# pd15.net
KiCad netlist of a schematic drawn in EAGLE
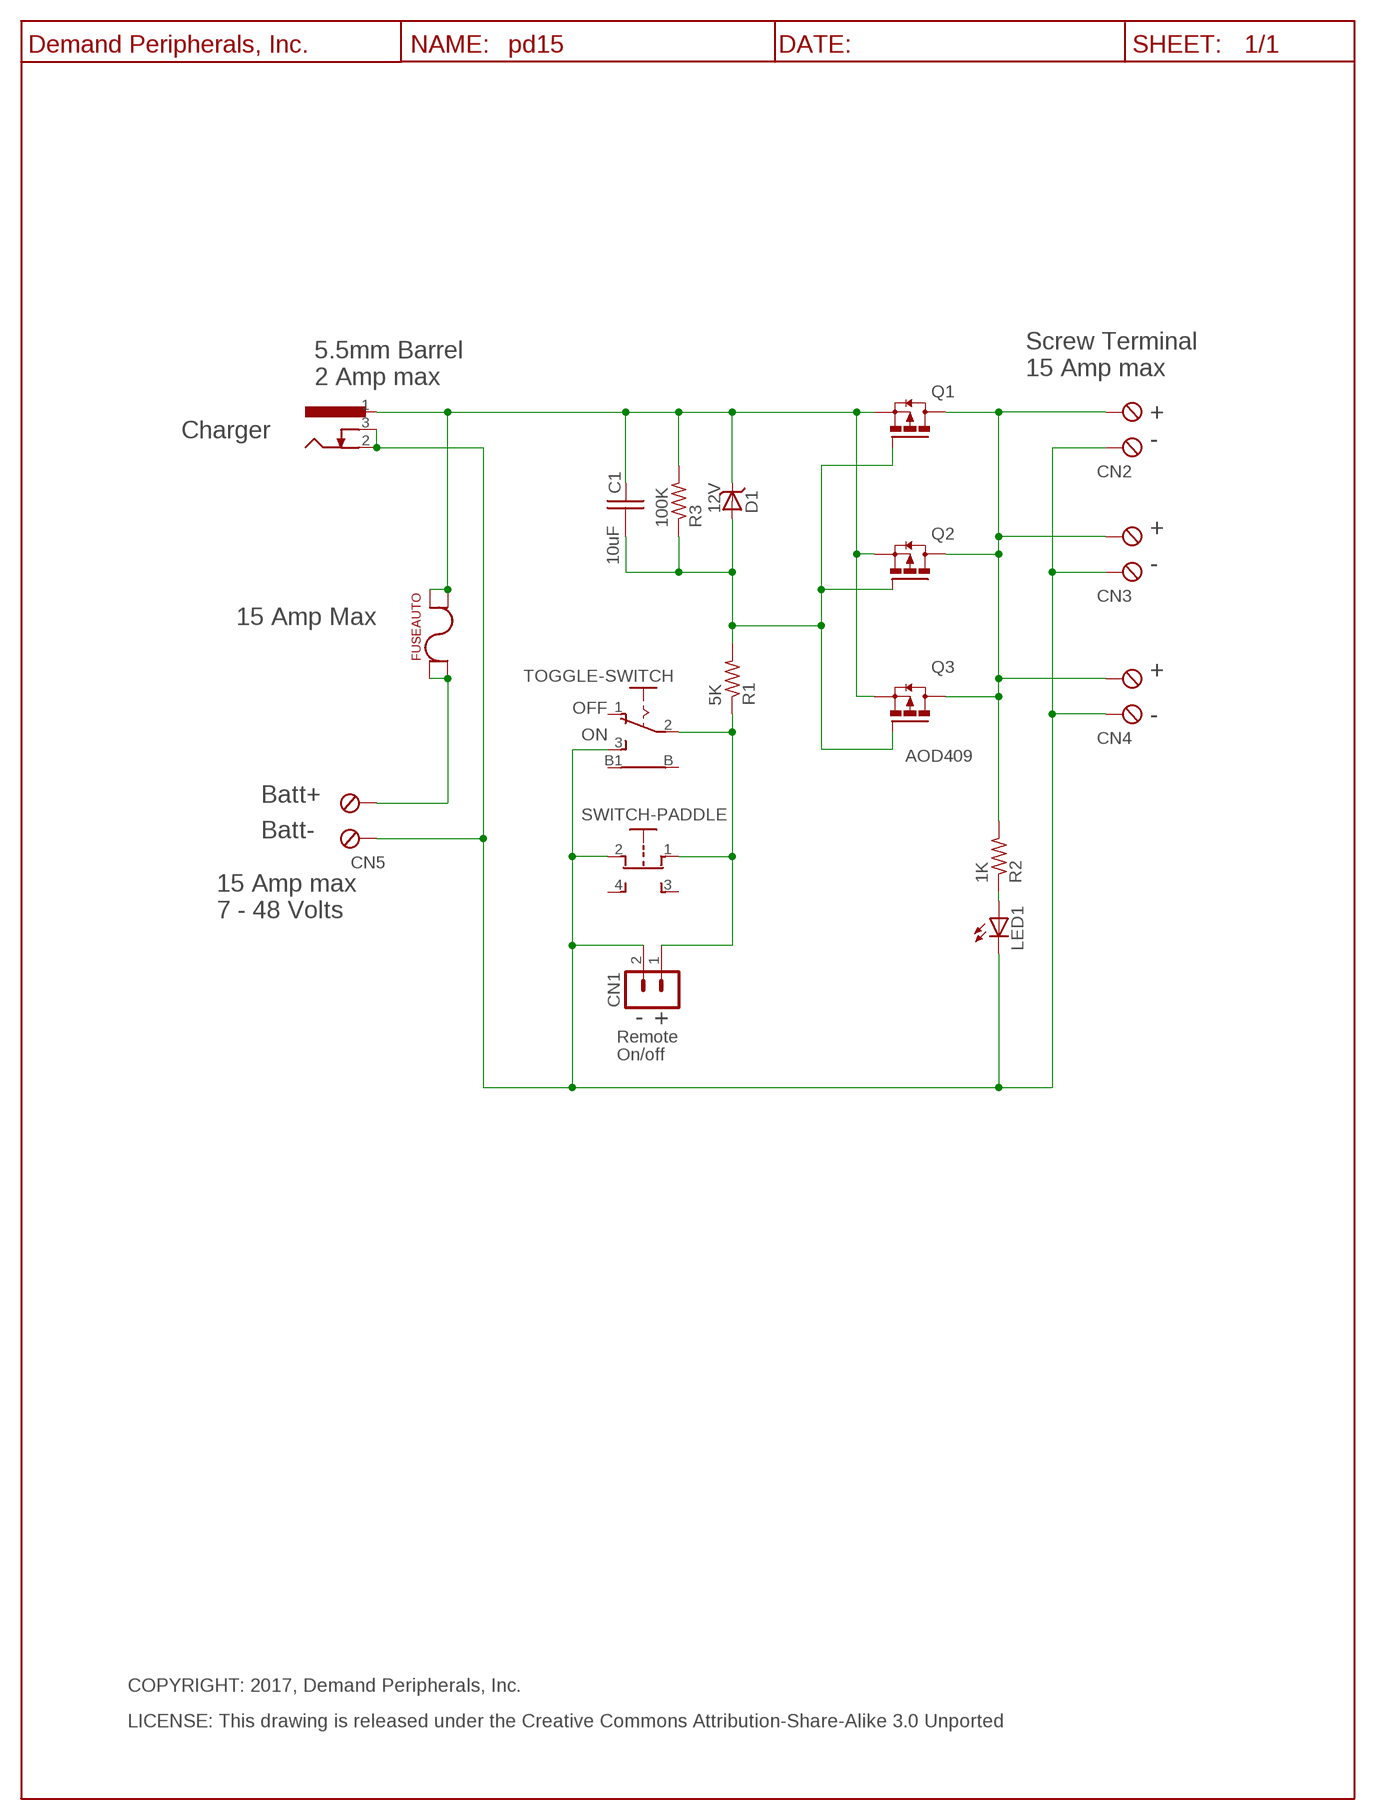
[diagram p0: schematic, sheet 1]

(export (version "E")
  (design (tool "Eeschema 10.0.6"))
  (components
    (comp (ref "C1")
      (value "10uF")
      (footprint "eagle-import:C0805")
      (libsource (lib "eagle-import") (part "C10UF35V_C0805"))
    )
    (comp (ref "CN1")
      (value "HDR-2X1-LCK")
      (footprint "eagle-import:HDR-2X1")
      (libsource (lib "eagle-import") (part "HDR-2X1-LCK"))
    )
    (comp (ref "CN2")
      (value "TBLK-5.08-X2")
      (footprint "eagle-import:TBLK-5.08-X2")
      (libsource (lib "eagle-import") (part "TBLK-5.08-X2"))
    )
    (comp (ref "CN3")
      (value "TBLK-5.08-X2")
      (footprint "eagle-import:TBLK-5.08-X2")
      (libsource (lib "eagle-import") (part "TBLK-5.08-X2"))
    )
    (comp (ref "CN4")
      (value "TBLK-5.08-X2")
      (footprint "eagle-import:TBLK-5.08-X2")
      (libsource (lib "eagle-import") (part "TBLK-5.08-X2"))
    )
    (comp (ref "CN5")
      (value "TBLK-5.08-X2")
      (footprint "eagle-import:TBLK-5.08-X2")
      (libsource (lib "eagle-import") (part "TBLK-5.08-X2"))
    )
    (comp (ref "D1")
      (value "12V")
      (footprint "eagle-import:SOD123")
      (libsource (lib "eagle-import") (part "BZT52C12"))
    )
    (comp (ref "FUSE")
      (value "FUSEAUTO")
      (footprint "eagle-import:KS3557-10")
      (libsource (lib "eagle-import") (part "FUSE-KS3557"))
    )
    (comp (ref "J1")
      (value "Barrel-5.5mm")
      (footprint "eagle-import:DC-BARREL-JACK-55MM")
      (libsource (lib "eagle-import") (part "DC-BARREL-JACK--55MM"))
    )
    (comp (ref "LED1")
      (value "LED-5MM-GRN")
      (footprint "eagle-import:LED5MM")
      (libsource (lib "eagle-import") (part "LED-5MM-GRN"))
    )
    (comp (ref "Q1")
      (value "FET_DPAK_P")
      (footprint "eagle-import:DPACK_TO-252")
      (libsource (lib "eagle-import") (part "AOD409"))
    )
    (comp (ref "Q2")
      (value "FET_DPAK_P")
      (footprint "eagle-import:DPACK_TO-252")
      (libsource (lib "eagle-import") (part "AOD409"))
    )
    (comp (ref "Q3")
      (value "AOD409")
      (footprint "eagle-import:DPACK_TO-252")
      (libsource (lib "eagle-import") (part "AOD409"))
    )
    (comp (ref "R1")
      (value "5K")
      (footprint "eagle-import:R0603")
      (libsource (lib "eagle-import") (part "R4.99K_R0603"))
    )
    (comp (ref "R2")
      (value "1K")
      (footprint "eagle-import:R0603")
      (libsource (lib "eagle-import") (part "R1K_R0603"))
    )
    (comp (ref "R3")
      (value "100K")
      (footprint "eagle-import:R0603")
      (libsource (lib "eagle-import") (part "R100K_R0603"))
    )
    (comp (ref "SW2")
      (value "SWITCH-PADDLE")
      (footprint "eagle-import:SWITCH-PADDLE")
      (libsource (lib "eagle-import") (part "SWITCH-PADDLE"))
    )
    (comp (ref "TOGGLE-SWITCH")
      (value "B12EH")
      (footprint "eagle-import:TOGGLE_SPDT_PC")
      (libsource (lib "eagle-import") (part "TOGGLE_SPDT_PC"))
    )
    (comp (ref "U$1")
      (value "DP_FRAME_P")
      (footprint "eagle-import:LETTER_P")
      (libsource (lib "eagle-import") (part "DP_FRAME_P"))
    )
  )
  (nets
    (net (code "1") (name "Net-(CN1-1)") (class "Default")
      (node (ref "CN1") (pin "2") (pinfunction "1_2") (pintype "passive"))
      (node (ref "CN2") (pin "1") (pinfunction "KL_1") (pintype "passive"))
      (node (ref "CN3") (pin "1") (pinfunction "KL_1") (pintype "passive"))
      (node (ref "CN4") (pin "1") (pinfunction "KL_1") (pintype "passive"))
      (node (ref "CN5") (pin "1") (pinfunction "KL_1") (pintype "passive"))
      (node (ref "J1") (pin "2") (pinfunction "2_2") (pintype "passive"))
      (node (ref "J1") (pin "3") (pinfunction "3_3") (pintype "passive"))
      (node (ref "LED1") (pin "C") (pinfunction "C_C") (pintype "passive"))
      (node (ref "SW2") (pin "2") (pinfunction "2_2") (pintype "passive"))
      (node (ref "TOGGLE-SWITCH") (pin "3") (pinfunction "S_3") (pintype "passive"))
    )
    (net (code "2") (name "Net-(CN1-2)") (class "Default")
      (node (ref "CN1") (pin "1") (pinfunction "2_1") (pintype "passive"))
      (node (ref "R1") (pin "1") (pinfunction "1_1") (pintype "passive"))
      (node (ref "SW2") (pin "1") (pinfunction "1_1") (pintype "passive"))
      (node (ref "TOGGLE-SWITCH") (pin "2") (pinfunction "P_2") (pintype "passive"))
    )
    (net (code "3") (name "Net-(CN2-KL1)") (class "Default")
      (node (ref "CN2") (pin "2") (pinfunction "KL1_2") (pintype "passive"))
      (node (ref "CN3") (pin "2") (pinfunction "KL1_2") (pintype "passive"))
      (node (ref "CN4") (pin "2") (pinfunction "KL1_2") (pintype "passive"))
      (node (ref "Q1") (pin "4") (pinfunction "D_4") (pintype "passive"))
      (node (ref "Q2") (pin "4") (pinfunction "D_4") (pintype "passive"))
      (node (ref "Q3") (pin "4") (pinfunction "D_4") (pintype "passive"))
      (node (ref "R2") (pin "2") (pinfunction "2_2") (pintype "passive"))
    )
    (net (code "4") (name "Net-(CN5-KL1)") (class "Default")
      (node (ref "CN5") (pin "2") (pinfunction "KL1_2") (pintype "passive"))
      (node (ref "FUSE") (pin "LS@1") (pinfunction "LS_LS@1") (pintype "power_in"))
      (node (ref "FUSE") (pin "LS@2") (pinfunction "LS_LS@2") (pintype "power_in"))
    )
    (net (code "5") (name "Net-(LED1-PadA)") (class "Default")
      (node (ref "LED1") (pin "A") (pinfunction "A_A") (pintype "passive"))
      (node (ref "R2") (pin "1") (pinfunction "1_1") (pintype "passive"))
    )
    (net (code "6") (name "Net-(Q1-G)") (class "Default")
      (node (ref "C1") (pin "2") (pinfunction "2_2") (pintype "passive"))
      (node (ref "D1") (pin "A") (pinfunction "A_A") (pintype "passive"))
      (node (ref "Q1") (pin "1") (pinfunction "G_1") (pintype "passive"))
      (node (ref "Q2") (pin "1") (pinfunction "G_1") (pintype "passive"))
      (node (ref "Q3") (pin "1") (pinfunction "G_1") (pintype "passive"))
      (node (ref "R1") (pin "2") (pinfunction "2_2") (pintype "passive"))
      (node (ref "R3") (pin "1") (pinfunction "1_1") (pintype "passive"))
    )
    (net (code "7") (name "Net-(Q1-S)") (class "Default")
      (node (ref "C1") (pin "1") (pinfunction "1_1") (pintype "passive"))
      (node (ref "D1") (pin "C") (pinfunction "C_C") (pintype "passive"))
      (node (ref "FUSE") (pin "RS@3") (pinfunction "RS_RS@3") (pintype "power_in"))
      (node (ref "FUSE") (pin "RS@4") (pinfunction "RS_RS@4") (pintype "power_in"))
      (node (ref "J1") (pin "1") (pinfunction "1_1") (pintype "passive"))
      (node (ref "Q1") (pin "3") (pinfunction "S_3") (pintype "passive"))
      (node (ref "Q2") (pin "3") (pinfunction "S_3") (pintype "passive"))
      (node (ref "Q3") (pin "3") (pinfunction "S_3") (pintype "passive"))
      (node (ref "R3") (pin "2") (pinfunction "2_2") (pintype "passive"))
    )
    (net (code "8") (name "unconnected-(SW2-Pad3)") (class "Default")
      (node (ref "SW2") (pin "3") (pinfunction "3_3") (pintype "passive"))
    )
    (net (code "9") (name "unconnected-(SW2-Pad4)") (class "Default")
      (node (ref "SW2") (pin "4") (pinfunction "4_4") (pintype "passive"))
    )
    (net (code "10") (name "unconnected-(TOGGLE-SWITCH-O-Pad1)") (class "Default")
      (node (ref "TOGGLE-SWITCH") (pin "1") (pinfunction "O_1") (pintype "passive"))
    )
    (net (code "11") (name "unconnected-(TOGGLE-SWITCH-PadB)") (class "Default")
      (node (ref "TOGGLE-SWITCH") (pin "B") (pinfunction "B_B") (pintype "passive"))
    )
    (net (code "12") (name "unconnected-(TOGGLE-SWITCH-PadB1)") (class "Default")
      (node (ref "TOGGLE-SWITCH") (pin "B1") (pinfunction "B1_B1") (pintype "passive"))
    )
  )
)
